# ge7_redraw.net
KiCad netlist of a schematic drawn in EAGLE
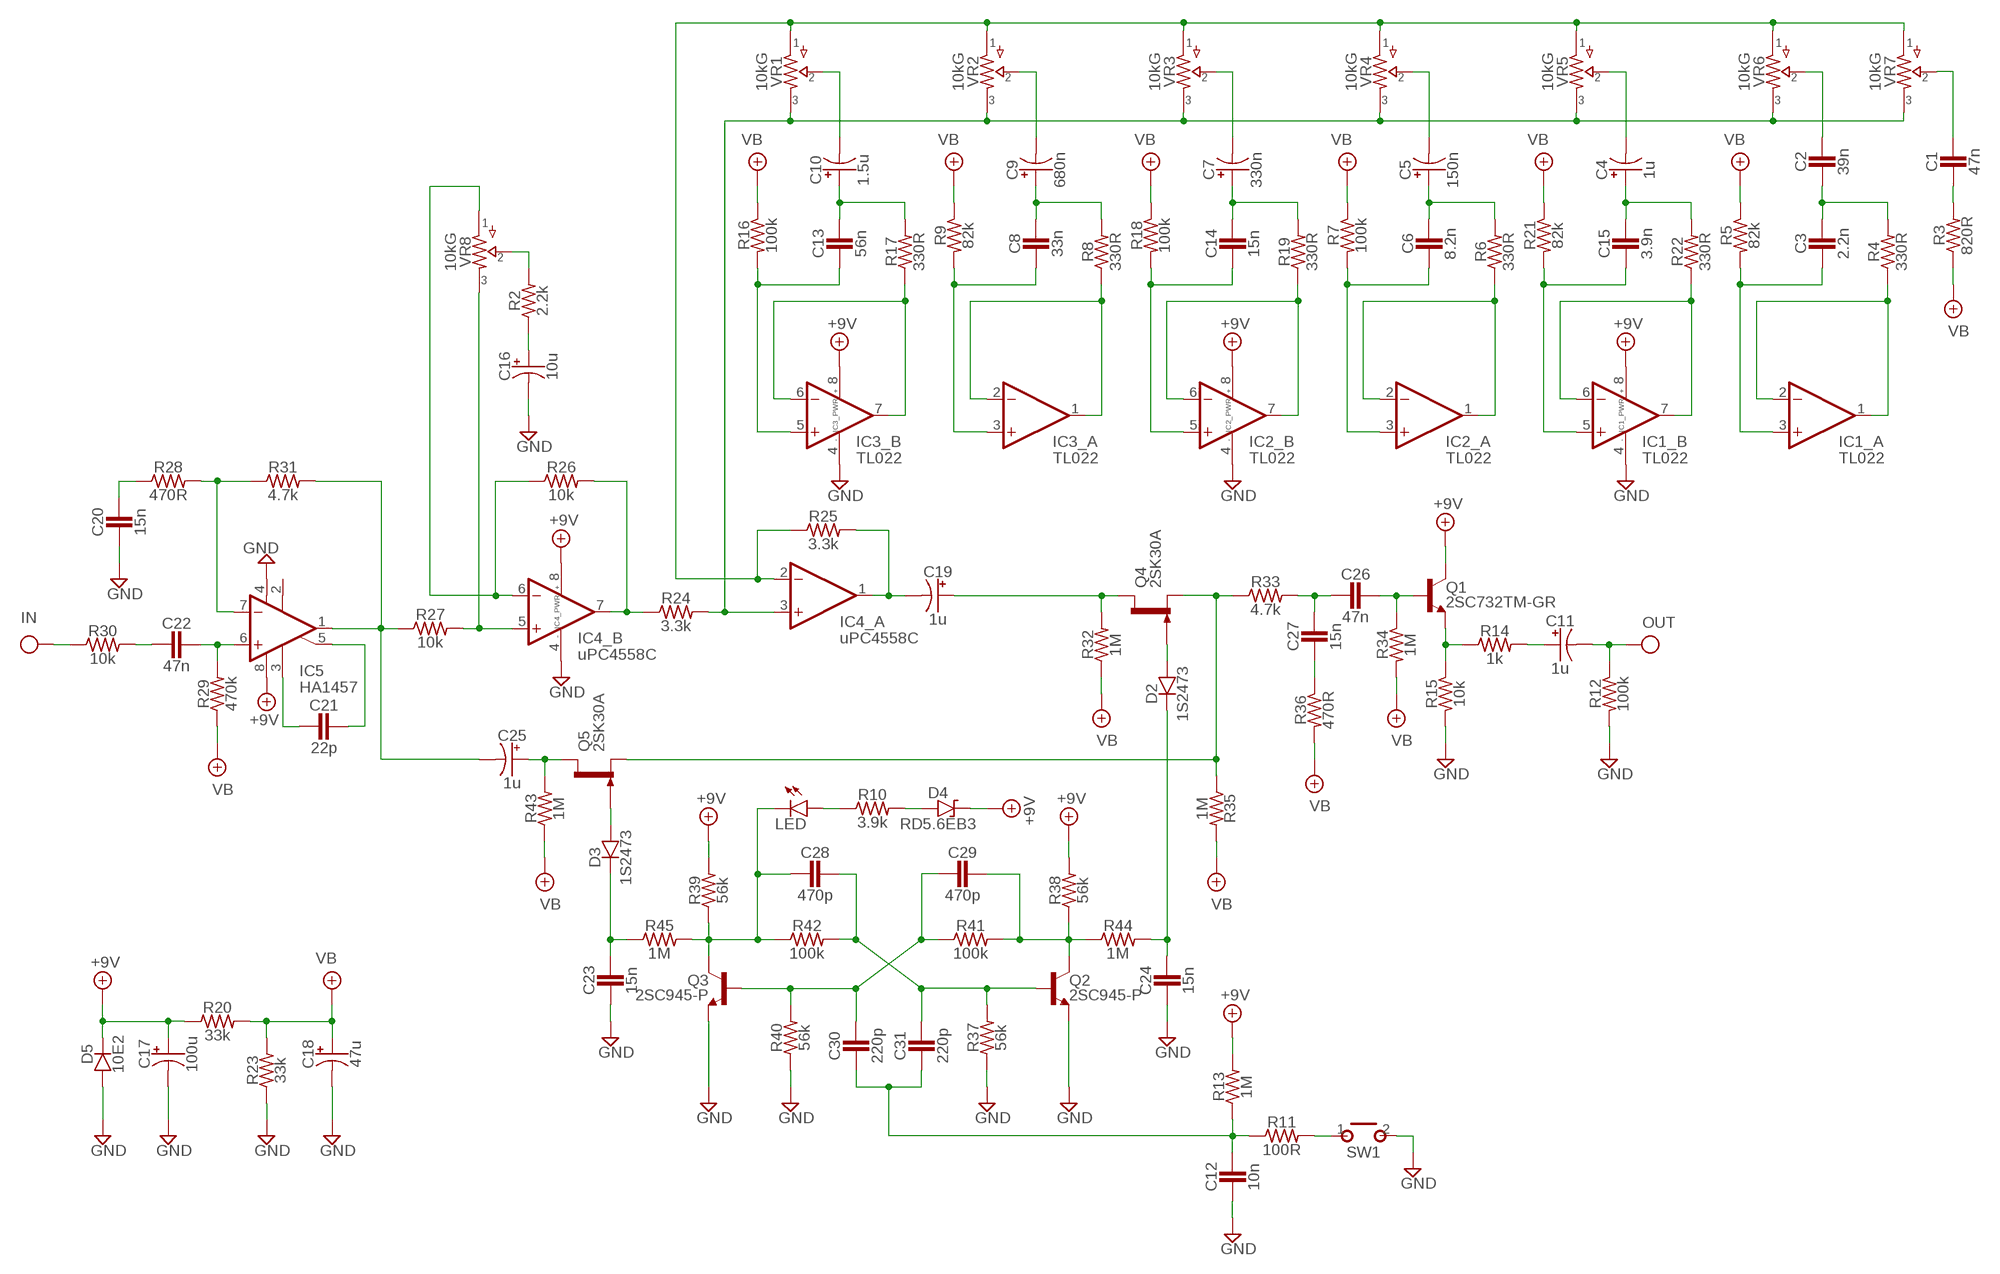
[diagram p0: schematic, sheet 1]

(export (version "E")
  (design (tool "Eeschema 10.0.6"))
  (components
    (comp (ref "C1")
      (value "47n")
      (footprint "eagle-import:BOX_SMALL")
      (libsource (lib "eagle-import") (part "CER/FILMBOX.1"))
    )
    (comp (ref "C2")
      (value "39n")
      (footprint "eagle-import:BOX_SMALL")
      (libsource (lib "eagle-import") (part "CER/FILMBOX.1"))
    )
    (comp (ref "C3")
      (value "2.2n")
      (footprint "eagle-import:BOX_SMALL")
      (libsource (lib "eagle-import") (part "CER/FILMBOX.1"))
    )
    (comp (ref "C4")
      (value "1u")
      (footprint "eagle-import:040_020")
      (libsource (lib "eagle-import") (part "0400"))
    )
    (comp (ref "C5")
      (value "150n")
      (footprint "eagle-import:040_020")
      (libsource (lib "eagle-import") (part "0400"))
    )
    (comp (ref "C6")
      (value "8.2n")
      (footprint "eagle-import:BOX_SMALL")
      (libsource (lib "eagle-import") (part "CER/FILMBOX.1"))
    )
    (comp (ref "C7")
      (value "330n")
      (footprint "eagle-import:040_020")
      (libsource (lib "eagle-import") (part "0400"))
    )
    (comp (ref "C8")
      (value "33n")
      (footprint "eagle-import:BOX_SMALL")
      (libsource (lib "eagle-import") (part "CER/FILMBOX.1"))
    )
    (comp (ref "C9")
      (value "680n")
      (footprint "eagle-import:040_020")
      (libsource (lib "eagle-import") (part "0400"))
    )
    (comp (ref "C10")
      (value "1.5u")
      (footprint "eagle-import:040_020")
      (libsource (lib "eagle-import") (part "0400"))
    )
    (comp (ref "C11")
      (value "1u")
      (footprint "eagle-import:040_020")
      (libsource (lib "eagle-import") (part "0400"))
    )
    (comp (ref "C12")
      (value "10n")
      (footprint "eagle-import:BOX_SMALL")
      (libsource (lib "eagle-import") (part "CER/FILMBOX.1"))
    )
    (comp (ref "C13")
      (value "56n")
      (footprint "eagle-import:BOX_SMALL")
      (libsource (lib "eagle-import") (part "CER/FILMBOX.1"))
    )
    (comp (ref "C14")
      (value "15n")
      (footprint "eagle-import:BOX_SMALL")
      (libsource (lib "eagle-import") (part "CER/FILMBOX.1"))
    )
    (comp (ref "C15")
      (value "3.9n")
      (footprint "eagle-import:BOX_SMALL")
      (libsource (lib "eagle-import") (part "CER/FILMBOX.1"))
    )
    (comp (ref "C16")
      (value "10u")
      (footprint "eagle-import:040_020")
      (libsource (lib "eagle-import") (part "0400"))
    )
    (comp (ref "C17")
      (value "100u")
      (footprint "eagle-import:040_020")
      (libsource (lib "eagle-import") (part "0400"))
    )
    (comp (ref "C18")
      (value "47u")
      (footprint "eagle-import:040_020")
      (libsource (lib "eagle-import") (part "0400"))
    )
    (comp (ref "C19")
      (value "1u")
      (footprint "eagle-import:040_020")
      (libsource (lib "eagle-import") (part "0400"))
    )
    (comp (ref "C20")
      (value "15n")
      (footprint "eagle-import:BOX_SMALL")
      (libsource (lib "eagle-import") (part "CER/FILMBOX.1"))
    )
    (comp (ref "C21")
      (value "22p")
      (footprint "eagle-import:BOX_SMALL")
      (libsource (lib "eagle-import") (part "CER/FILMBOX.1"))
    )
    (comp (ref "C22")
      (value "47n")
      (footprint "eagle-import:BOX_SMALL")
      (libsource (lib "eagle-import") (part "CER/FILMBOX.1"))
    )
    (comp (ref "C23")
      (value "15n")
      (footprint "eagle-import:BOX_SMALL")
      (libsource (lib "eagle-import") (part "CER/FILMBOX.1"))
    )
    (comp (ref "C24")
      (value "15n")
      (footprint "eagle-import:BOX_SMALL")
      (libsource (lib "eagle-import") (part "CER/FILMBOX.1"))
    )
    (comp (ref "C25")
      (value "1u")
      (footprint "eagle-import:040_020")
      (libsource (lib "eagle-import") (part "0400"))
    )
    (comp (ref "C26")
      (value "47n")
      (footprint "eagle-import:BOX_SMALL")
      (libsource (lib "eagle-import") (part "CER/FILMBOX.1"))
    )
    (comp (ref "C27")
      (value "15n")
      (footprint "eagle-import:BOX_SMALL")
      (libsource (lib "eagle-import") (part "CER/FILMBOX.1"))
    )
    (comp (ref "C28")
      (value "470p")
      (footprint "eagle-import:BOX_SMALL")
      (libsource (lib "eagle-import") (part "CER/FILMBOX.1"))
    )
    (comp (ref "C29")
      (value "470p")
      (footprint "eagle-import:BOX_SMALL")
      (libsource (lib "eagle-import") (part "CER/FILMBOX.1"))
    )
    (comp (ref "C30")
      (value "220p")
      (footprint "eagle-import:BOX_SMALL")
      (libsource (lib "eagle-import") (part "CER/FILMBOX.1"))
    )
    (comp (ref "C31")
      (value "220p")
      (footprint "eagle-import:BOX_SMALL")
      (libsource (lib "eagle-import") (part "CER/FILMBOX.1"))
    )
    (comp (ref "D2")
      (value "1S2473")
      (footprint "eagle-import:DO35-2")
      (libsource (lib "eagle-import") (part "DO35.2"))
    )
    (comp (ref "D3")
      (value "1S2473")
      (footprint "eagle-import:DO35-2")
      (libsource (lib "eagle-import") (part "DO35.2"))
    )
    (comp (ref "D4")
      (value "RD5.6EB3")
      (footprint "eagle-import:DO41-2")
      (libsource (lib "eagle-import") (part "ZENER.2"))
    )
    (comp (ref "D5")
      (value "10E2")
      (footprint "eagle-import:DO35-2")
      (libsource (lib "eagle-import") (part "DO35.2"))
    )
    (comp (ref "IC1")
      (value "TL022")
      (footprint "eagle-import:DIL0")
      (libsource (lib "eagle-import") (part "DUALTH"))
    )
    (comp (ref "IC2")
      (value "TL022")
      (footprint "eagle-import:DIL0")
      (libsource (lib "eagle-import") (part "DUALTH"))
    )
    (comp (ref "IC3")
      (value "TL022")
      (footprint "eagle-import:DIL0")
      (libsource (lib "eagle-import") (part "DUALTH"))
    )
    (comp (ref "IC4")
      (value "uPC4558C")
      (footprint "eagle-import:DIL0")
      (libsource (lib "eagle-import") (part "DUALTH"))
    )
    (comp (ref "IC5")
      (value "HA1457")
      (footprint "eagle-import:SIL8")
      (libsource (lib "eagle-import") (part "HA1457"))
    )
    (comp (ref "LED")
      (value "LED")
      (footprint "eagle-import:3MM_D")
      (libsource (lib "eagle-import") (part "LED"))
    )
    (comp (ref "Q1")
      (value "2SC732TM-GR")
      (footprint "eagle-import:TO92-")
      (libsource (lib "eagle-import") (part "2SC828A"))
    )
    (comp (ref "Q2")
      (value "2SC945-P")
      (footprint "eagle-import:TO92-")
      (libsource (lib "eagle-import") (part "2SC828A"))
    )
    (comp (ref "Q3")
      (value "2SC945-P")
      (footprint "eagle-import:TO92-")
      (libsource (lib "eagle-import") (part "2SC828A"))
    )
    (comp (ref "Q4")
      (value "2SK30A")
      (footprint "eagle-import:TO92-")
      (libsource (lib "eagle-import") (part "2N5457"))
    )
    (comp (ref "Q5")
      (value "2SK30A")
      (footprint "eagle-import:TO92-")
      (libsource (lib "eagle-import") (part "2N5457"))
    )
    (comp (ref "R2")
      (value "2.2k")
      (footprint "eagle-import:R0207_3")
      (libsource (lib "eagle-import") (part "R_.3B"))
    )
    (comp (ref "R3")
      (value "820R")
      (footprint "eagle-import:R0207_3")
      (libsource (lib "eagle-import") (part "R_.3B"))
    )
    (comp (ref "R4")
      (value "330R")
      (footprint "eagle-import:R0207_3")
      (libsource (lib "eagle-import") (part "R_.3B"))
    )
    (comp (ref "R5")
      (value "82k")
      (footprint "eagle-import:R0207_3")
      (libsource (lib "eagle-import") (part "R_.3B"))
    )
    (comp (ref "R6")
      (value "330R")
      (footprint "eagle-import:R0207_3")
      (libsource (lib "eagle-import") (part "R_.3B"))
    )
    (comp (ref "R7")
      (value "100k")
      (footprint "eagle-import:R0207_3")
      (libsource (lib "eagle-import") (part "R_.3B"))
    )
    (comp (ref "R8")
      (value "330R")
      (footprint "eagle-import:R0207_3")
      (libsource (lib "eagle-import") (part "R_.3B"))
    )
    (comp (ref "R9")
      (value "82k")
      (footprint "eagle-import:R0207_3")
      (libsource (lib "eagle-import") (part "R_.3B"))
    )
    (comp (ref "R10")
      (value "3.9k")
      (footprint "eagle-import:R0207_3")
      (libsource (lib "eagle-import") (part "R_.3B"))
    )
    (comp (ref "R11")
      (value "100R")
      (footprint "eagle-import:R0207_3")
      (libsource (lib "eagle-import") (part "R_.3B"))
    )
    (comp (ref "R12")
      (value "100k")
      (footprint "eagle-import:R0207_3")
      (libsource (lib "eagle-import") (part "R_.3B"))
    )
    (comp (ref "R13")
      (value "1M")
      (footprint "eagle-import:R0207_3")
      (libsource (lib "eagle-import") (part "R_.3B"))
    )
    (comp (ref "R14")
      (value "1k")
      (footprint "eagle-import:R0207_3")
      (libsource (lib "eagle-import") (part "R_.3B"))
    )
    (comp (ref "R15")
      (value "10k")
      (footprint "eagle-import:R0207_3")
      (libsource (lib "eagle-import") (part "R_.3B"))
    )
    (comp (ref "R16")
      (value "100k")
      (footprint "eagle-import:R0207_3")
      (libsource (lib "eagle-import") (part "R_.3B"))
    )
    (comp (ref "R17")
      (value "330R")
      (footprint "eagle-import:R0207_3")
      (libsource (lib "eagle-import") (part "R_.3B"))
    )
    (comp (ref "R18")
      (value "100k")
      (footprint "eagle-import:R0207_3")
      (libsource (lib "eagle-import") (part "R_.3B"))
    )
    (comp (ref "R19")
      (value "330R")
      (footprint "eagle-import:R0207_3")
      (libsource (lib "eagle-import") (part "R_.3B"))
    )
    (comp (ref "R20")
      (value "33k")
      (footprint "eagle-import:R0207_3")
      (libsource (lib "eagle-import") (part "R_.3B"))
    )
    (comp (ref "R21")
      (value "82k")
      (footprint "eagle-import:R0207_3")
      (libsource (lib "eagle-import") (part "R_.3B"))
    )
    (comp (ref "R22")
      (value "330R")
      (footprint "eagle-import:R0207_3")
      (libsource (lib "eagle-import") (part "R_.3B"))
    )
    (comp (ref "R23")
      (value "33k")
      (footprint "eagle-import:R0207_3")
      (libsource (lib "eagle-import") (part "R_.3B"))
    )
    (comp (ref "R24")
      (value "3.3k")
      (footprint "eagle-import:R0207_3")
      (libsource (lib "eagle-import") (part "R_.3B"))
    )
    (comp (ref "R25")
      (value "3.3k")
      (footprint "eagle-import:R0207_3")
      (libsource (lib "eagle-import") (part "R_.3B"))
    )
    (comp (ref "R26")
      (value "10k")
      (footprint "eagle-import:R0207_3")
      (libsource (lib "eagle-import") (part "R_.3B"))
    )
    (comp (ref "R27")
      (value "10k")
      (footprint "eagle-import:R0207_3")
      (libsource (lib "eagle-import") (part "R_.3B"))
    )
    (comp (ref "R28")
      (value "470R")
      (footprint "eagle-import:R0207_3")
      (libsource (lib "eagle-import") (part "R_.3B"))
    )
    (comp (ref "R29")
      (value "470k")
      (footprint "eagle-import:R0207_3")
      (libsource (lib "eagle-import") (part "R_.3B"))
    )
    (comp (ref "R30")
      (value "10k")
      (footprint "eagle-import:R0207_3")
      (libsource (lib "eagle-import") (part "R_.3B"))
    )
    (comp (ref "R31")
      (value "4.7k")
      (footprint "eagle-import:R0207_3")
      (libsource (lib "eagle-import") (part "R_.3B"))
    )
    (comp (ref "R32")
      (value "1M")
      (footprint "eagle-import:R0207_3")
      (libsource (lib "eagle-import") (part "R_.3B"))
    )
    (comp (ref "R33")
      (value "4.7k")
      (footprint "eagle-import:R0207_3")
      (libsource (lib "eagle-import") (part "R_.3B"))
    )
    (comp (ref "R34")
      (value "1M")
      (footprint "eagle-import:R0207_3")
      (libsource (lib "eagle-import") (part "R_.3B"))
    )
    (comp (ref "R35")
      (value "1M")
      (footprint "eagle-import:R0207_3")
      (libsource (lib "eagle-import") (part "R_.3B"))
    )
    (comp (ref "R36")
      (value "470R")
      (footprint "eagle-import:R0207_3")
      (libsource (lib "eagle-import") (part "R_.3B"))
    )
    (comp (ref "R37")
      (value "56k")
      (footprint "eagle-import:R0207_3")
      (libsource (lib "eagle-import") (part "R_.3B"))
    )
    (comp (ref "R38")
      (value "56k")
      (footprint "eagle-import:R0207_3")
      (libsource (lib "eagle-import") (part "R_.3B"))
    )
    (comp (ref "R39")
      (value "56k")
      (footprint "eagle-import:R0207_3")
      (libsource (lib "eagle-import") (part "R_.3B"))
    )
    (comp (ref "R40")
      (value "56k")
      (footprint "eagle-import:R0207_3")
      (libsource (lib "eagle-import") (part "R_.3B"))
    )
    (comp (ref "R41")
      (value "100k")
      (footprint "eagle-import:R0207_3")
      (libsource (lib "eagle-import") (part "R_.3B"))
    )
    (comp (ref "R42")
      (value "100k")
      (footprint "eagle-import:R0207_3")
      (libsource (lib "eagle-import") (part "R_.3B"))
    )
    (comp (ref "R43")
      (value "1M")
      (footprint "eagle-import:R0207_3")
      (libsource (lib "eagle-import") (part "R_.3B"))
    )
    (comp (ref "R44")
      (value "1M")
      (footprint "eagle-import:R0207_3")
      (libsource (lib "eagle-import") (part "R_.3B"))
    )
    (comp (ref "R45")
      (value "1M")
      (footprint "eagle-import:R0207_3")
      (libsource (lib "eagle-import") (part "R_.3B"))
    )
    (comp (ref "SW1")
      (value "MOMENTARY")
      (footprint "eagle-import:SPST")
      (libsource (lib "eagle-import") (part "MOMENTARY"))
    )
    (comp (ref "VR1")
      (value "10kG")
      (footprint "eagle-import:16MM")
      (libsource (lib "eagle-import") (part "POTS16MM"))
    )
    (comp (ref "VR2")
      (value "10kG")
      (footprint "eagle-import:16MM")
      (libsource (lib "eagle-import") (part "POTS16MM"))
    )
    (comp (ref "VR3")
      (value "10kG")
      (footprint "eagle-import:16MM")
      (libsource (lib "eagle-import") (part "POTS16MM"))
    )
    (comp (ref "VR4")
      (value "10kG")
      (footprint "eagle-import:16MM")
      (libsource (lib "eagle-import") (part "POTS16MM"))
    )
    (comp (ref "VR5")
      (value "10kG")
      (footprint "eagle-import:16MM")
      (libsource (lib "eagle-import") (part "POTS16MM"))
    )
    (comp (ref "VR6")
      (value "10kG")
      (footprint "eagle-import:16MM")
      (libsource (lib "eagle-import") (part "POTS16MM"))
    )
    (comp (ref "VR7")
      (value "10kG")
      (footprint "eagle-import:16MM")
      (libsource (lib "eagle-import") (part "POTS16MM"))
    )
    (comp (ref "VR8")
      (value "10kG")
      (footprint "eagle-import:16MM")
      (libsource (lib "eagle-import") (part "POTS16MM"))
    )
  )
  (nets
    (net (code "1") (name "+9V") (class "Default")
      (node (ref "C17") (pin "+") (pinfunction "+_+") (pintype "passive"))
      (node (ref "D4") (pin "C") (pinfunction "C_C") (pintype "passive"))
      (node (ref "D5") (pin "C") (pinfunction "C_C") (pintype "passive"))
      (node (ref "IC1") (pin "8") (pinfunction "V+_8") (pintype "power_in"))
      (node (ref "IC2") (pin "8") (pinfunction "V+_8") (pintype "power_in"))
      (node (ref "IC3") (pin "8") (pinfunction "V+_8") (pintype "power_in"))
      (node (ref "IC4") (pin "8") (pinfunction "V+_8") (pintype "power_in"))
      (node (ref "IC5") (pin "8") (pinfunction "V+_8") (pintype "power_in"))
      (node (ref "Q1") (pin "2") (pinfunction "C_2") (pintype "passive"))
      (node (ref "R13") (pin "2") (pinfunction "2_2") (pintype "passive"))
      (node (ref "R20") (pin "1") (pinfunction "1_1") (pintype "passive"))
      (node (ref "R38") (pin "2") (pinfunction "2_2") (pintype "passive"))
      (node (ref "R39") (pin "2") (pinfunction "2_2") (pintype "passive"))
    )
    (net (code "2") (name "GND") (class "Default")
      (node (ref "C12") (pin "2") (pinfunction "2_2") (pintype "passive"))
      (node (ref "C16") (pin "-") (pinfunction "-_-") (pintype "passive"))
      (node (ref "C17") (pin "-") (pinfunction "-_-") (pintype "passive"))
      (node (ref "C18") (pin "-") (pinfunction "-_-") (pintype "passive"))
      (node (ref "C20") (pin "2") (pinfunction "2_2") (pintype "passive"))
      (node (ref "C23") (pin "2") (pinfunction "2_2") (pintype "passive"))
      (node (ref "C24") (pin "2") (pinfunction "2_2") (pintype "passive"))
      (node (ref "D5") (pin "A") (pinfunction "A_A") (pintype "passive"))
      (node (ref "IC1") (pin "4") (pinfunction "V-_4") (pintype "power_in"))
      (node (ref "IC2") (pin "4") (pinfunction "V-_4") (pintype "power_in"))
      (node (ref "IC3") (pin "4") (pinfunction "V-_4") (pintype "power_in"))
      (node (ref "IC4") (pin "4") (pinfunction "V-_4") (pintype "power_in"))
      (node (ref "IC5") (pin "4") (pinfunction "V-_4") (pintype "power_in"))
      (node (ref "Q2") (pin "3") (pinfunction "E_3") (pintype "passive"))
      (node (ref "Q3") (pin "3") (pinfunction "E_3") (pintype "passive"))
      (node (ref "R12") (pin "2") (pinfunction "2_2") (pintype "passive"))
      (node (ref "R15") (pin "2") (pinfunction "2_2") (pintype "passive"))
      (node (ref "R23") (pin "1") (pinfunction "1_1") (pintype "passive"))
      (node (ref "R37") (pin "1") (pinfunction "1_1") (pintype "passive"))
      (node (ref "R40") (pin "1") (pinfunction "1_1") (pintype "passive"))
      (node (ref "SW1") (pin "2") (pinfunction "S_2") (pintype "passive"))
    )
    (net (code "3") (name "IN") (class "Default")
      (node (ref "R30") (pin "1") (pinfunction "1_1") (pintype "passive"))
    )
    (net (code "4") (name "Net-(C1-Pad1)") (class "Default")
      (node (ref "C1") (pin "1") (pinfunction "1_1") (pintype "passive"))
      (node (ref "VR7") (pin "2") (pinfunction "2_2") (pintype "passive"))
    )
    (net (code "5") (name "Net-(C1-Pad2)") (class "Default")
      (node (ref "C1") (pin "2") (pinfunction "2_2") (pintype "passive"))
      (node (ref "R3") (pin "2") (pinfunction "2_2") (pintype "passive"))
    )
    (net (code "6") (name "Net-(C2-Pad1)") (class "Default")
      (node (ref "C2") (pin "1") (pinfunction "1_1") (pintype "passive"))
      (node (ref "VR6") (pin "2") (pinfunction "2_2") (pintype "passive"))
    )
    (net (code "7") (name "Net-(C2-Pad2)") (class "Default")
      (node (ref "C2") (pin "2") (pinfunction "2_2") (pintype "passive"))
      (node (ref "C3") (pin "1") (pinfunction "1_1") (pintype "passive"))
      (node (ref "R4") (pin "2") (pinfunction "2_2") (pintype "passive"))
    )
    (net (code "8") (name "Net-(C4-Pad-)") (class "Default")
      (node (ref "C4") (pin "-") (pinfunction "-_-") (pintype "passive"))
      (node (ref "VR5") (pin "2") (pinfunction "2_2") (pintype "passive"))
    )
    (net (code "9") (name "Net-(C5-Pad+)") (class "Default")
      (node (ref "C5") (pin "+") (pinfunction "+_+") (pintype "passive"))
      (node (ref "C6") (pin "1") (pinfunction "1_1") (pintype "passive"))
      (node (ref "R6") (pin "2") (pinfunction "2_2") (pintype "passive"))
    )
    (net (code "10") (name "Net-(C5-Pad-)") (class "Default")
      (node (ref "C5") (pin "-") (pinfunction "-_-") (pintype "passive"))
      (node (ref "VR4") (pin "2") (pinfunction "2_2") (pintype "passive"))
    )
    (net (code "11") (name "Net-(C7-Pad-)") (class "Default")
      (node (ref "C7") (pin "-") (pinfunction "-_-") (pintype "passive"))
      (node (ref "VR3") (pin "2") (pinfunction "2_2") (pintype "passive"))
    )
    (net (code "12") (name "Net-(C8-Pad1)") (class "Default")
      (node (ref "C8") (pin "1") (pinfunction "1_1") (pintype "passive"))
      (node (ref "C9") (pin "+") (pinfunction "+_+") (pintype "passive"))
      (node (ref "R8") (pin "2") (pinfunction "2_2") (pintype "passive"))
    )
    (net (code "13") (name "Net-(C9-Pad-)") (class "Default")
      (node (ref "C9") (pin "-") (pinfunction "-_-") (pintype "passive"))
      (node (ref "VR2") (pin "2") (pinfunction "2_2") (pintype "passive"))
    )
    (net (code "14") (name "Net-(C10-Pad+)") (class "Default")
      (node (ref "C10") (pin "+") (pinfunction "+_+") (pintype "passive"))
      (node (ref "C13") (pin "1") (pinfunction "1_1") (pintype "passive"))
      (node (ref "R17") (pin "2") (pinfunction "2_2") (pintype "passive"))
    )
    (net (code "15") (name "Net-(C10-Pad-)") (class "Default")
      (node (ref "C10") (pin "-") (pinfunction "-_-") (pintype "passive"))
      (node (ref "VR1") (pin "2") (pinfunction "2_2") (pintype "passive"))
    )
    (net (code "16") (name "Net-(C11-Pad+)") (class "Default")
      (node (ref "C11") (pin "+") (pinfunction "+_+") (pintype "passive"))
      (node (ref "R14") (pin "2") (pinfunction "2_2") (pintype "passive"))
    )
    (net (code "17") (name "Net-(C12-Pad1)") (class "Default")
      (node (ref "C12") (pin "1") (pinfunction "1_1") (pintype "passive"))
      (node (ref "C30") (pin "2") (pinfunction "2_2") (pintype "passive"))
      (node (ref "C31") (pin "2") (pinfunction "2_2") (pintype "passive"))
      (node (ref "R11") (pin "1") (pinfunction "1_1") (pintype "passive"))
      (node (ref "R13") (pin "1") (pinfunction "1_1") (pintype "passive"))
    )
    (net (code "18") (name "Net-(C14-Pad1)") (class "Default")
      (node (ref "C14") (pin "1") (pinfunction "1_1") (pintype "passive"))
      (node (ref "C7") (pin "+") (pinfunction "+_+") (pintype "passive"))
      (node (ref "R19") (pin "2") (pinfunction "2_2") (pintype "passive"))
    )
    (net (code "19") (name "Net-(C15-Pad1)") (class "Default")
      (node (ref "C15") (pin "1") (pinfunction "1_1") (pintype "passive"))
      (node (ref "C4") (pin "+") (pinfunction "+_+") (pintype "passive"))
      (node (ref "R22") (pin "2") (pinfunction "2_2") (pintype "passive"))
    )
    (net (code "20") (name "Net-(C16-Pad+)") (class "Default")
      (node (ref "C16") (pin "+") (pinfunction "+_+") (pintype "passive"))
      (node (ref "R2") (pin "1") (pinfunction "1_1") (pintype "passive"))
    )
    (net (code "21") (name "Net-(C20-Pad1)") (class "Default")
      (node (ref "C20") (pin "1") (pinfunction "1_1") (pintype "passive"))
      (node (ref "R28") (pin "1") (pinfunction "1_1") (pintype "passive"))
    )
    (net (code "22") (name "Net-(C22-Pad2)") (class "Default")
      (node (ref "C22") (pin "2") (pinfunction "2_2") (pintype "passive"))
      (node (ref "R30") (pin "2") (pinfunction "2_2") (pintype "passive"))
    )
    (net (code "23") (name "Net-(C23-Pad1)") (class "Default")
      (node (ref "C23") (pin "1") (pinfunction "1_1") (pintype "passive"))
      (node (ref "D3") (pin "C") (pinfunction "C_C") (pintype "passive"))
      (node (ref "R45") (pin "1") (pinfunction "1_1") (pintype "passive"))
    )
    (net (code "24") (name "Net-(C24-Pad1)") (class "Default")
      (node (ref "C24") (pin "1") (pinfunction "1_1") (pintype "passive"))
      (node (ref "D2") (pin "C") (pinfunction "C_C") (pintype "passive"))
      (node (ref "R44") (pin "2") (pinfunction "2_2") (pintype "passive"))
    )
    (net (code "25") (name "Net-(C26-Pad2)") (class "Default")
      (node (ref "C26") (pin "2") (pinfunction "2_2") (pintype "passive"))
      (node (ref "C27") (pin "1") (pinfunction "1_1") (pintype "passive"))
      (node (ref "R33") (pin "2") (pinfunction "2_2") (pintype "passive"))
    )
    (net (code "26") (name "Net-(C27-Pad2)") (class "Default")
      (node (ref "C27") (pin "2") (pinfunction "2_2") (pintype "passive"))
      (node (ref "R36") (pin "1") (pinfunction "1_1") (pintype "passive"))
    )
    (net (code "27") (name "Net-(D4-PadA)") (class "Default")
      (node (ref "D4") (pin "A") (pinfunction "A_A") (pintype "passive"))
      (node (ref "R10") (pin "2") (pinfunction "2_2") (pintype "passive"))
    )
    (net (code "28") (name "Net-(IC1A-+IN)") (class "Default")
      (node (ref "C3") (pin "2") (pinfunction "2_2") (pintype "passive"))
      (node (ref "IC1") (pin "3") (pinfunction "+IN_3") (pintype "input"))
      (node (ref "R5") (pin "2") (pinfunction "2_2") (pintype "passive"))
    )
    (net (code "29") (name "Net-(IC1A--IN)") (class "Default")
      (node (ref "IC1") (pin "1") (pinfunction "OUT_1") (pintype "output"))
      (node (ref "IC1") (pin "2") (pinfunction "-IN_2") (pintype "input"))
      (node (ref "R4") (pin "1") (pinfunction "1_1") (pintype "passive"))
    )
    (net (code "30") (name "Net-(IC1B-+IN)") (class "Default")
      (node (ref "C15") (pin "2") (pinfunction "2_2") (pintype "passive"))
      (node (ref "IC1") (pin "5") (pinfunction "+IN_5") (pintype "input"))
      (node (ref "R21") (pin "2") (pinfunction "2_2") (pintype "passive"))
    )
    (net (code "31") (name "Net-(IC1B--IN)") (class "Default")
      (node (ref "IC1") (pin "6") (pinfunction "-IN_6") (pintype "input"))
      (node (ref "IC1") (pin "7") (pinfunction "OUT_7") (pintype "output"))
      (node (ref "R22") (pin "1") (pinfunction "1_1") (pintype "passive"))
    )
    (net (code "32") (name "Net-(IC2A-+IN)") (class "Default")
      (node (ref "C6") (pin "2") (pinfunction "2_2") (pintype "passive"))
      (node (ref "IC2") (pin "3") (pinfunction "+IN_3") (pintype "input"))
      (node (ref "R7") (pin "2") (pinfunction "2_2") (pintype "passive"))
    )
    (net (code "33") (name "Net-(IC2A--IN)") (class "Default")
      (node (ref "IC2") (pin "1") (pinfunction "OUT_1") (pintype "output"))
      (node (ref "IC2") (pin "2") (pinfunction "-IN_2") (pintype "input"))
      (node (ref "R6") (pin "1") (pinfunction "1_1") (pintype "passive"))
    )
    (net (code "34") (name "Net-(IC2B-+IN)") (class "Default")
      (node (ref "C14") (pin "2") (pinfunction "2_2") (pintype "passive"))
      (node (ref "IC2") (pin "5") (pinfunction "+IN_5") (pintype "input"))
      (node (ref "R18") (pin "2") (pinfunction "2_2") (pintype "passive"))
    )
    (net (code "35") (name "Net-(IC2B--IN)") (class "Default")
      (node (ref "IC2") (pin "6") (pinfunction "-IN_6") (pintype "input"))
      (node (ref "IC2") (pin "7") (pinfunction "OUT_7") (pintype "output"))
      (node (ref "R19") (pin "1") (pinfunction "1_1") (pintype "passive"))
    )
    (net (code "36") (name "Net-(IC3A-+IN)") (class "Default")
      (node (ref "C8") (pin "2") (pinfunction "2_2") (pintype "passive"))
      (node (ref "IC3") (pin "3") (pinfunction "+IN_3") (pintype "input"))
      (node (ref "R9") (pin "2") (pinfunction "2_2") (pintype "passive"))
    )
    (net (code "37") (name "Net-(IC3A--IN)") (class "Default")
      (node (ref "IC3") (pin "1") (pinfunction "OUT_1") (pintype "output"))
      (node (ref "IC3") (pin "2") (pinfunction "-IN_2") (pintype "input"))
      (node (ref "R8") (pin "1") (pinfunction "1_1") (pintype "passive"))
    )
    (net (code "38") (name "Net-(IC3B-+IN)") (class "Default")
      (node (ref "C13") (pin "2") (pinfunction "2_2") (pintype "passive"))
      (node (ref "IC3") (pin "5") (pinfunction "+IN_5") (pintype "input"))
      (node (ref "R16") (pin "2") (pinfunction "2_2") (pintype "passive"))
    )
    (net (code "39") (name "Net-(IC3B--IN)") (class "Default")
      (node (ref "IC3") (pin "6") (pinfunction "-IN_6") (pintype "input"))
      (node (ref "IC3") (pin "7") (pinfunction "OUT_7") (pintype "output"))
      (node (ref "R17") (pin "1") (pinfunction "1_1") (pintype "passive"))
    )
    (net (code "40") (name "Net-(IC4A-+IN)") (class "Default")
      (node (ref "IC4") (pin "3") (pinfunction "+IN_3") (pintype "input"))
      (node (ref "R24") (pin "2") (pinfunction "2_2") (pintype "passive"))
      (node (ref "VR1") (pin "3") (pinfunction "3_3") (pintype "passive"))
      (node (ref "VR2") (pin "3") (pinfunction "3_3") (pintype "passive"))
      (node (ref "VR3") (pin "3") (pinfunction "3_3") (pintype "passive"))
      (node (ref "VR4") (pin "3") (pinfunction "3_3") (pintype "passive"))
      (node (ref "VR5") (pin "3") (pinfunction "3_3") (pintype "passive"))
      (node (ref "VR6") (pin "3") (pinfunction "3_3") (pintype "passive"))
      (node (ref "VR7") (pin "3") (pinfunction "3_3") (pintype "passive"))
    )
    (net (code "41") (name "Net-(IC4A--IN)") (class "Default")
      (node (ref "IC4") (pin "2") (pinfunction "-IN_2") (pintype "input"))
      (node (ref "R25") (pin "1") (pinfunction "1_1") (pintype "passive"))
      (node (ref "VR1") (pin "1") (pinfunction "1_1") (pintype "passive"))
      (node (ref "VR2") (pin "1") (pinfunction "1_1") (pintype "passive"))
      (node (ref "VR3") (pin "1") (pinfunction "1_1") (pintype "passive"))
      (node (ref "VR4") (pin "1") (pinfunction "1_1") (pintype "passive"))
      (node (ref "VR5") (pin "1") (pinfunction "1_1") (pintype "passive"))
      (node (ref "VR6") (pin "1") (pinfunction "1_1") (pintype "passive"))
      (node (ref "VR7") (pin "1") (pinfunction "1_1") (pintype "passive"))
    )
    (net (code "42") (name "Net-(IC4A-OUT)") (class "Default")
      (node (ref "C19") (pin "-") (pinfunction "-_-") (pintype "passive"))
      (node (ref "IC4") (pin "1") (pinfunction "OUT_1") (pintype "output"))
      (node (ref "R25") (pin "2") (pinfunction "2_2") (pintype "passive"))
    )
    (net (code "43") (name "Net-(IC4B-+IN)") (class "Default")
      (node (ref "IC4") (pin "5") (pinfunction "+IN_5") (pintype "input"))
      (node (ref "R27") (pin "2") (pinfunction "2_2") (pintype "passive"))
      (node (ref "VR8") (pin "3") (pinfunction "3_3") (pintype "passive"))
    )
    (net (code "44") (name "Net-(IC4B--IN)") (class "Default")
      (node (ref "IC4") (pin "6") (pinfunction "-IN_6") (pintype "input"))
      (node (ref "R26") (pin "1") (pinfunction "1_1") (pintype "passive"))
      (node (ref "VR8") (pin "1") (pinfunction "1_1") (pintype "passive"))
    )
    (net (code "45") (name "Net-(IC4B-OUT)") (class "Default")
      (node (ref "IC4") (pin "7") (pinfunction "OUT_7") (pintype "output"))
      (node (ref "R24") (pin "1") (pinfunction "1_1") (pintype "passive"))
      (node (ref "R26") (pin "2") (pinfunction "2_2") (pintype "passive"))
    )
    (net (code "46") (name "Net-(IC5-+IN)") (class "Default")
      (node (ref "C22") (pin "1") (pinfunction "1_1") (pintype "passive"))
      (node (ref "IC5") (pin "6") (pinfunction "+IN_6") (pintype "input"))
      (node (ref "R29") (pin "2") (pinfunction "2_2") (pintype "passive"))
    )
    (net (code "47") (name "Net-(IC5--IN)") (class "Default")
      (node (ref "IC5") (pin "7") (pinfunction "-IN_7") (pintype "input"))
      (node (ref "R28") (pin "2") (pinfunction "2_2") (pintype "passive"))
      (node (ref "R31") (pin "1") (pinfunction "1_1") (pintype "passive"))
    )
    (net (code "48") (name "Net-(IC5-ON1)") (class "Default")
      (node (ref "C21") (pin "2") (pinfunction "2_2") (pintype "passive"))
      (node (ref "IC5") (pin "3") (pinfunction "ON1_3") (pintype "passive"))
    )
    (net (code "49") (name "Net-(IC5-ON2)") (class "Default")
      (node (ref "C21") (pin "1") (pinfunction "1_1") (pintype "passive"))
      (node (ref "IC5") (pin "5") (pinfunction "ON2_5") (pintype "passive"))
    )
    (net (code "50") (name "Net-(IC5-OUT)") (class "Default")
      (node (ref "C25") (pin "-") (pinfunction "-_-") (pintype "passive"))
      (node (ref "IC5") (pin "1") (pinfunction "OUT_1") (pintype "output"))
      (node (ref "R27") (pin "1") (pinfunction "1_1") (pintype "passive"))
      (node (ref "R31") (pin "2") (pinfunction "2_2") (pintype "passive"))
    )
    (net (code "51") (name "Net-(LED-A)") (class "Default")
      (node (ref "LED") (pin "ANODE") (pinfunction "A_ANODE") (pintype "passive"))
      (node (ref "R10") (pin "1") (pinfunction "1_1") (pintype "passive"))
    )
    (net (code "52") (name "Net-(LED-C)") (class "Default")
      (node (ref "C28") (pin "2") (pinfunction "2_2") (pintype "passive"))
      (node (ref "LED") (pin "P$1") (pinfunction "C_P$1") (pintype "passive"))
      (node (ref "Q3") (pin "2") (pinfunction "C_2") (pintype "passive"))
      (node (ref "R39") (pin "1") (pinfunction "1_1") (pintype "passive"))
      (node (ref "R42") (pin "1") (pinfunction "1_1") (pintype "passive"))
      (node (ref "R45") (pin "2") (pinfunction "2_2") (pintype "passive"))
    )
    (net (code "53") (name "Net-(Q1-B)") (class "Default")
      (node (ref "C26") (pin "1") (pinfunction "1_1") (pintype "passive"))
      (node (ref "Q1") (pin "1") (pinfunction "B_1") (pintype "passive"))
      (node (ref "R34") (pin "1") (pinfunction "1_1") (pintype "passive"))
    )
    (net (code "54") (name "Net-(Q1-E)") (class "Default")
      (node (ref "Q1") (pin "3") (pinfunction "E_3") (pintype "passive"))
      (node (ref "R14") (pin "1") (pinfunction "1_1") (pintype "passive"))
      (node (ref "R15") (pin "1") (pinfunction "1_1") (pintype "passive"))
    )
    (net (code "55") (name "Net-(Q2-B)") (class "Default")
      (node (ref "C28") (pin "1") (pinfunction "1_1") (pintype "passive"))
      (node (ref "C31") (pin "1") (pinfunction "1_1") (pintype "passive"))
      (node (ref "Q2") (pin "1") (pinfunction "B_1") (pintype "passive"))
      (node (ref "R37") (pin "2") (pinfunction "2_2") (pintype "passive"))
      (node (ref "R42") (pin "2") (pinfunction "2_2") (pintype "passive"))
    )
    (net (code "56") (name "Net-(Q2-C)") (class "Default")
      (node (ref "C29") (pin "1") (pinfunction "1_1") (pintype "passive"))
      (node (ref "Q2") (pin "2") (pinfunction "C_2") (pintype "passive"))
      (node (ref "R38") (pin "1") (pinfunction "1_1") (pintype "passive"))
      (node (ref "R41") (pin "2") (pinfunction "2_2") (pintype "passive"))
      (node (ref "R44") (pin "1") (pinfunction "1_1") (pintype "passive"))
    )
    (net (code "57") (name "Net-(Q3-B)") (class "Default")
      (node (ref "C29") (pin "2") (pinfunction "2_2") (pintype "passive"))
      (node (ref "C30") (pin "1") (pinfunction "1_1") (pintype "passive"))
      (node (ref "Q3") (pin "1") (pinfunction "B_1") (pintype "passive"))
      (node (ref "R40") (pin "2") (pinfunction "2_2") (pintype "passive"))
      (node (ref "R41") (pin "1") (pinfunction "1_1") (pintype "passive"))
    )
    (net (code "58") (name "Net-(Q4-D)") (class "Default")
      (node (ref "C19") (pin "+") (pinfunction "+_+") (pintype "passive"))
      (node (ref "Q4") (pin "3") (pinfunction "D_3") (pintype "passive"))
      (node (ref "R32") (pin "2") (pinfunction "2_2") (pintype "passive"))
    )
    (net (code "59") (name "Net-(Q4-G)") (class "Default")
      (node (ref "D2") (pin "A") (pinfunction "A_A") (pintype "passive"))
      (node (ref "Q4") (pin "1") (pinfunction "G_1") (pintype "passive"))
    )
    (net (code "60") (name "Net-(Q4-S)") (class "Default")
      (node (ref "Q4") (pin "2") (pinfunction "S_2") (pintype "passive"))
      (node (ref "Q5") (pin "2") (pinfunction "S_2") (pintype "passive"))
      (node (ref "R33") (pin "1") (pinfunction "1_1") (pintype "passive"))
      (node (ref "R35") (pin "1") (pinfunction "1_1") (pintype "passive"))
    )
    (net (code "61") (name "Net-(Q5-D)") (class "Default")
      (node (ref "C25") (pin "+") (pinfunction "+_+") (pintype "passive"))
      (node (ref "Q5") (pin "3") (pinfunction "D_3") (pintype "passive"))
      (node (ref "R43") (pin "2") (pinfunction "2_2") (pintype "passive"))
    )
    (net (code "62") (name "Net-(Q5-G)") (class "Default")
      (node (ref "D3") (pin "A") (pinfunction "A_A") (pintype "passive"))
      (node (ref "Q5") (pin "1") (pinfunction "G_1") (pintype "passive"))
    )
    (net (code "63") (name "Net-(R2-Pad2)") (class "Default")
      (node (ref "R2") (pin "2") (pinfunction "2_2") (pintype "passive"))
      (node (ref "VR8") (pin "2") (pinfunction "2_2") (pintype "passive"))
    )
    (net (code "64") (name "Net-(SW1-P)") (class "Default")
      (node (ref "R11") (pin "2") (pinfunction "2_2") (pintype "passive"))
      (node (ref "SW1") (pin "1") (pinfunction "P_1") (pintype "passive"))
    )
    (net (code "65") (name "OUT") (class "Default")
      (node (ref "C11") (pin "-") (pinfunction "-_-") (pintype "passive"))
      (node (ref "R12") (pin "1") (pinfunction "1_1") (pintype "passive"))
    )
    (net (code "66") (name "VB") (class "Default")
      (node (ref "C18") (pin "+") (pinfunction "+_+") (pintype "passive"))
      (node (ref "R16") (pin "1") (pinfunction "1_1") (pintype "passive"))
      (node (ref "R18") (pin "1") (pinfunction "1_1") (pintype "passive"))
      (node (ref "R20") (pin "2") (pinfunction "2_2") (pintype "passive"))
      (node (ref "R21") (pin "1") (pinfunction "1_1") (pintype "passive"))
      (node (ref "R23") (pin "2") (pinfunction "2_2") (pintype "passive"))
      (node (ref "R29") (pin "1") (pinfunction "1_1") (pintype "passive"))
      (node (ref "R3") (pin "1") (pinfunction "1_1") (pintype "passive"))
      (node (ref "R32") (pin "1") (pinfunction "1_1") (pintype "passive"))
      (node (ref "R34") (pin "2") (pinfunction "2_2") (pintype "passive"))
      (node (ref "R35") (pin "2") (pinfunction "2_2") (pintype "passive"))
      (node (ref "R36") (pin "2") (pinfunction "2_2") (pintype "passive"))
      (node (ref "R43") (pin "1") (pinfunction "1_1") (pintype "passive"))
      (node (ref "R5") (pin "1") (pinfunction "1_1") (pintype "passive"))
      (node (ref "R7") (pin "1") (pinfunction "1_1") (pintype "passive"))
      (node (ref "R9") (pin "1") (pinfunction "1_1") (pintype "passive"))
    )
    (net (code "67") (name "unconnected-(IC5-OPT-Pad2)") (class "Default")
      (node (ref "IC5") (pin "2") (pinfunction "OPT_2") (pintype "passive"))
    )
  )
)
